# idealdiode.net
KiCad netlist of a schematic drawn in EAGLE
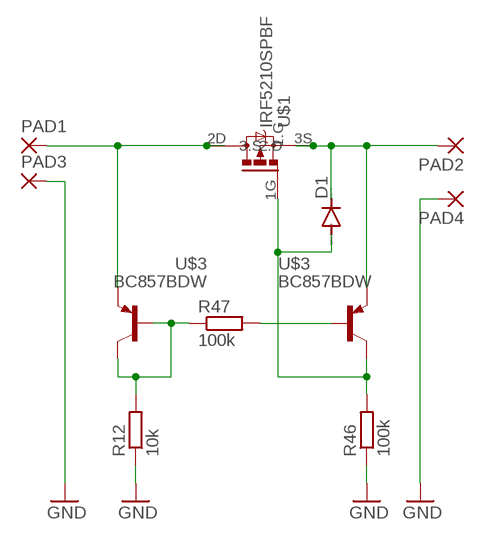
[diagram p0: schematic, sheet 1]

(export (version "E")
  (design (tool "Eeschema 10.0.6"))
  (components
    (comp (ref "D1")
      (value "DIODE-SMB")
      (footprint "eagle-import:SMB")
      (libsource (lib "eagle-import") (part "DIODE-SMB"))
    )
    (comp (ref "PAD1")
      (value "2,54/1,0")
      (footprint "eagle-import:2,54_1,0")
      (libsource (lib "eagle-import") (part "2,54/1,0"))
    )
    (comp (ref "PAD2")
      (value "2,54/1,0")
      (footprint "eagle-import:2,54_1,0")
      (libsource (lib "eagle-import") (part "2,54/1,0"))
    )
    (comp (ref "PAD3")
      (value "2,54/1,0")
      (footprint "eagle-import:2,54_1,0")
      (libsource (lib "eagle-import") (part "2,54/1,0"))
    )
    (comp (ref "PAD4")
      (value "2,54/1,0")
      (footprint "eagle-import:2,54_1,0")
      (libsource (lib "eagle-import") (part "2,54/1,0"))
    )
    (comp (ref "R12")
      (value "10k")
      (footprint "eagle-import:R0603")
      (libsource (lib "eagle-import") (part "R-EU_R0603"))
    )
    (comp (ref "R46")
      (value "100k")
      (footprint "eagle-import:R0603")
      (libsource (lib "eagle-import") (part "R-EU_R0603"))
    )
    (comp (ref "R47")
      (value "100k")
      (footprint "eagle-import:R0603")
      (libsource (lib "eagle-import") (part "R-EU_R0603"))
    )
    (comp (ref "U$1")
      (value "IRF5210SPBF")
      (footprint "eagle-import:TO-220SMD")
      (libsource (lib "eagle-import") (part "IRF5210SPBF"))
    )
    (comp (ref "U$3")
      (value "BC857BDW")
      (footprint "eagle-import:SOT363-INFINION")
      (libsource (lib "eagle-import") (part "BC857BDW"))
    )
  )
  (nets
    (net (code "1") (name "GND") (class "Default")
      (node (ref "PAD3") (pin "1") (pinfunction "P_1") (pintype "passive"))
      (node (ref "PAD4") (pin "1") (pinfunction "P_1") (pintype "passive"))
      (node (ref "R12") (pin "1") (pinfunction "1_1") (pintype "passive"))
      (node (ref "R46") (pin "1") (pinfunction "1_1") (pintype "passive"))
    )
    (net (code "2") (name "Net-(PAD1-P)") (class "Default")
      (node (ref "PAD1") (pin "1") (pinfunction "P_1") (pintype "passive"))
      (node (ref "U$1") (pin "2D") (pinfunction "2.D_2D") (pintype "bidirectional"))
      (node (ref "U$3") (pin "1") (pinfunction "E1_1") (pintype "passive"))
    )
    (net (code "3") (name "Net-(PAD2-P)") (class "Default")
      (node (ref "D1") (pin "C") (pinfunction "C_C") (pintype "passive"))
      (node (ref "PAD2") (pin "1") (pinfunction "P_1") (pintype "passive"))
      (node (ref "U$1") (pin "3S") (pinfunction "3.S_3S") (pintype "bidirectional"))
      (node (ref "U$3") (pin "4") (pinfunction "E_4") (pintype "passive"))
    )
    (net (code "4") (name "Net-(U$1-1.G)") (class "Default")
      (node (ref "D1") (pin "A") (pinfunction "A_A") (pintype "passive"))
      (node (ref "R46") (pin "2") (pinfunction "2_2") (pintype "passive"))
      (node (ref "U$1") (pin "1G") (pinfunction "1.G_1G") (pintype "bidirectional"))
      (node (ref "U$3") (pin "3") (pinfunction "C_3") (pintype "passive"))
    )
    (net (code "5") (name "Net-(U$3-B)") (class "Default")
      (node (ref "R47") (pin "2") (pinfunction "2_2") (pintype "passive"))
      (node (ref "U$3") (pin "5") (pinfunction "B_5") (pintype "passive"))
    )
    (net (code "6") (name "Net-(U$3-B1)") (class "Default")
      (node (ref "R12") (pin "2") (pinfunction "2_2") (pintype "passive"))
      (node (ref "R47") (pin "1") (pinfunction "1_1") (pintype "passive"))
      (node (ref "U$3") (pin "2") (pinfunction "B1_2") (pintype "passive"))
      (node (ref "U$3") (pin "6") (pinfunction "C1_6") (pintype "passive"))
    )
  )
)
